# VectorModulator.net
KiCad netlist of a schematic drawn in Altium Designer
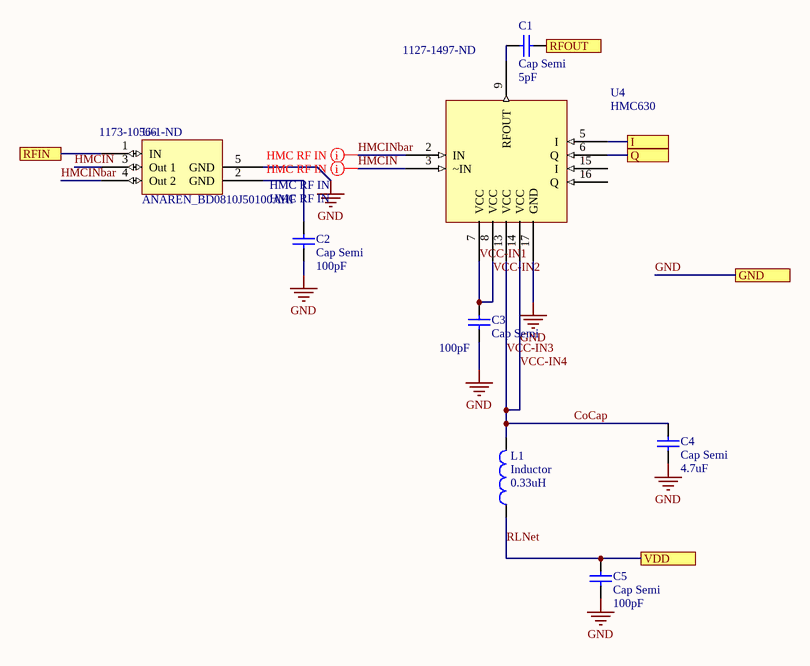
[diagram p0: VectorModulator.SchDoc]

(export (version "E")
  (design (tool "Eeschema 10.0.6"))
  (components
    (comp (ref "C1")
      (value "Cap Semi")
      (footprint "0402")
      (description "Capacitor (Semiconductor SIM Model)")
      (fields (field (name "ALTIUM_VALUE") "5pF") (field (name "PUBLISHER") "Altium Limited"))
      (libsource (lib "Miscellaneous Devices") (part "Cap Semi"))
    )
    (comp (ref "C2")
      (value "Cap Semi")
      (footprint "0402")
      (description "Capacitor (Semiconductor SIM Model)")
      (fields (field (name "ALTIUM_VALUE") "100pF") (field (name "PUBLISHER") "Altium Limited"))
      (libsource (lib "Miscellaneous Devices") (part "Cap Semi"))
    )
    (comp (ref "C3")
      (value "Cap Semi")
      (footprint "0402")
      (description "Capacitor (Semiconductor SIM Model)")
      (fields (field (name "ALTIUM_VALUE") "100pF") (field (name "PUBLISHER") "Altium Limited"))
      (libsource (lib "Miscellaneous Devices") (part "Cap Semi"))
    )
    (comp (ref "C4")
      (value "Cap Semi")
      (footprint "0402")
      (description "Capacitor (Semiconductor SIM Model)")
      (fields (field (name "ALTIUM_VALUE") "4.7uF") (field (name "PUBLISHER") "Altium Limited"))
      (libsource (lib "Miscellaneous Devices") (part "Cap Semi"))
    )
    (comp (ref "C5")
      (value "Cap Semi")
      (footprint "0402")
      (description "Capacitor (Semiconductor SIM Model)")
      (fields (field (name "ALTIUM_VALUE") "100pF") (field (name "PUBLISHER") "Altium Limited"))
      (libsource (lib "Miscellaneous Devices") (part "Cap Semi"))
    )
    (comp (ref "L1")
      (value "Inductor")
      (footprint "0402-A")
      (fields (field (name "ALTIUM_VALUE") "0.33uH") (field (name "PUBLISHER") "Altium Limited"))
      (libsource (lib "Miscellaneous Devices") (part "Inductor"))
    )
    (comp (ref "U4")
      (value "HMC630")
      (footprint "*QFN50P300X300X100-17N")
      (fields (field (name "SUPPLIER PART NUMBER 1") "1127-1497-ND"))
      (libsource (lib "wcsng_altium") (part "HMC630"))
    )
    (comp (ref "U6")
      (value "ANAREN_BD0810J50100AHF")
      (footprint "*ANAREN_PD0409J7575S2HF")
      (fields (field (name "SUPPLIER PART NUMBER 1") "1173-1056-1-ND"))
      (libsource (lib "wcsng_altium") (part "ANAREN_BD0810J50100AHF"))
    )
  )
  (nets
    (net (code "1") (name "/CoCap") (class "Default")
      (node (ref "C4") (pin "2") (pinfunction "2_2") (pintype "passive"))
      (node (ref "L1") (pin "2") (pinfunction "2_2") (pintype "passive"))
      (node (ref "U4") (pin "13") (pinfunction "VCC_13") (pintype "power_in"))
      (node (ref "U4") (pin "14") (pinfunction "VCC_14") (pintype "power_in"))
    )
    (net (code "2") (name "/HMCIN") (class "Default")
      (node (ref "U4") (pin "3") (pinfunction "~IN_3") (pintype "input"))
      (node (ref "U6") (pin "3") (pinfunction "Out_1_3") (pintype "bidirectional"))
    )
    (net (code "3") (name "/HMCINbar") (class "Default")
      (node (ref "U4") (pin "2") (pinfunction "IN_2") (pintype "input"))
      (node (ref "U6") (pin "4") (pinfunction "Out_2_4") (pintype "bidirectional"))
    )
    (net (code "4") (name "/I") (class "Default")
      (node (ref "U4") (pin "5") (pinfunction "I_5") (pintype "input"))
    )
    (net (code "5") (name "/Q") (class "Default")
      (node (ref "U4") (pin "6") (pinfunction "Q_6") (pintype "input"))
    )
    (net (code "6") (name "/RFIN") (class "Default")
      (node (ref "U6") (pin "1") (pinfunction "IN_1") (pintype "bidirectional"))
    )
    (net (code "7") (name "/RFOUT") (class "Default")
      (node (ref "C1") (pin "2") (pinfunction "2_2") (pintype "passive"))
    )
    (net (code "8") (name "/RLNet") (class "Default")
      (node (ref "C5") (pin "2") (pinfunction "2_2") (pintype "passive"))
      (node (ref "L1") (pin "1") (pinfunction "1_1") (pintype "passive"))
    )
    (net (code "9") (name "/VCC-IN1") (class "Default")
      (node (ref "C3") (pin "2") (pinfunction "2_2") (pintype "passive"))
      (node (ref "U4") (pin "7") (pinfunction "VCC_7") (pintype "power_in"))
      (node (ref "U4") (pin "8") (pinfunction "VCC_8") (pintype "power_in"))
    )
    (net (code "10") (name "GND") (class "Default")
      (node (ref "C2") (pin "1") (pinfunction "1_1") (pintype "passive"))
      (node (ref "C3") (pin "1") (pinfunction "1_1") (pintype "passive"))
      (node (ref "C4") (pin "1") (pinfunction "1_1") (pintype "passive"))
      (node (ref "C5") (pin "1") (pinfunction "1_1") (pintype "passive"))
      (node (ref "U4") (pin "17") (pinfunction "GND_17") (pintype "power_in"))
      (node (ref "U6") (pin "5") (pinfunction "GND_5") (pintype "power_in"))
    )
    (net (code "11") (name "Net-(C2-Pad2)") (class "Default")
      (node (ref "C2") (pin "2") (pinfunction "2_2") (pintype "passive"))
      (node (ref "U6") (pin "2") (pinfunction "GND_2") (pintype "power_in"))
    )
    (net (code "12") (name "Net-(U4-RFOUT)") (class "Default")
      (node (ref "C1") (pin "1") (pinfunction "1_1") (pintype "passive"))
      (node (ref "U4") (pin "9") (pinfunction "RFOUT_9") (pintype "output"))
    )
    (net (code "13") (name "unconnected-(U4-I-Pad15)") (class "Default")
      (node (ref "U4") (pin "15") (pinfunction "I_15") (pintype "input"))
    )
    (net (code "14") (name "unconnected-(U4-Q-Pad16)") (class "Default")
      (node (ref "U4") (pin "16") (pinfunction "Q_16") (pintype "input"))
    )
  )
)
